# simpleledboard.net
KiCad netlist of a schematic drawn in EAGLE
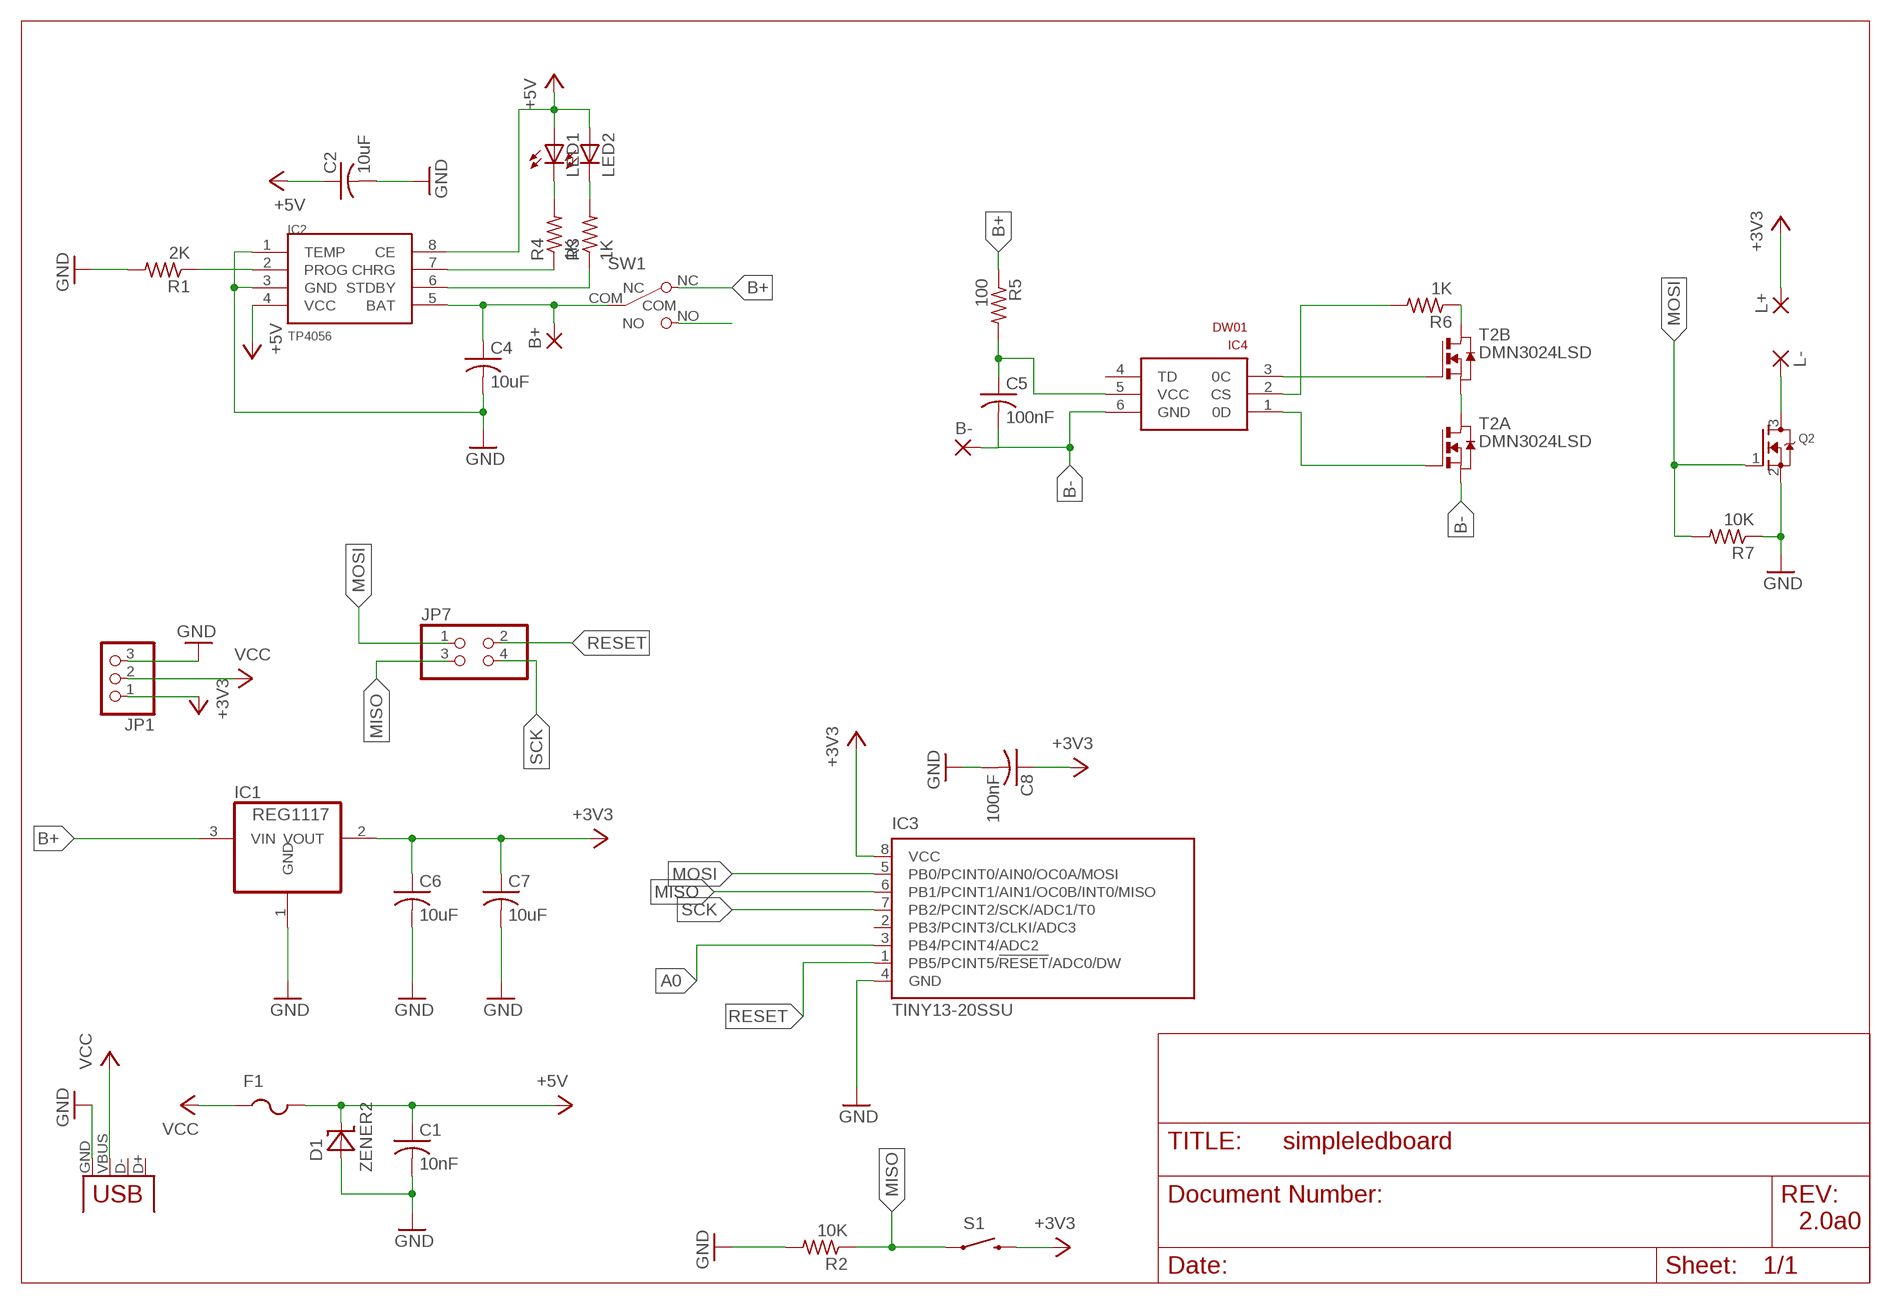
[diagram p0: schematic, sheet 1]

(export (version "E")
  (design (tool "Eeschema 10.0.6"))
  (components
    (comp (ref "B+")
      (value "WIREPADSMD1,27-254")
      (footprint "eagle-import:SMD1,27-2,54")
      (libsource (lib "eagle-import") (part "WIREPADSMD1,27-254"))
    )
    (comp (ref "B-")
      (value "WIREPADSMD1,27-254")
      (footprint "eagle-import:SMD1,27-2,54")
      (libsource (lib "eagle-import") (part "WIREPADSMD1,27-254"))
    )
    (comp (ref "C1")
      (value "10nF")
      (footprint "eagle-import:C0603")
      (libsource (lib "eagle-import") (part "C-USC0603"))
    )
    (comp (ref "C2")
      (value "10uF")
      (footprint "eagle-import:C0603")
      (libsource (lib "eagle-import") (part "C-USC0603"))
    )
    (comp (ref "C4")
      (value "10uF")
      (footprint "eagle-import:C0603")
      (libsource (lib "eagle-import") (part "C-USC0603"))
    )
    (comp (ref "C5")
      (value "100nF")
      (footprint "eagle-import:C0603")
      (libsource (lib "eagle-import") (part "C-USC0603"))
    )
    (comp (ref "C6")
      (value "10uF")
      (footprint "eagle-import:C0603")
      (libsource (lib "eagle-import") (part "C-USC0603"))
    )
    (comp (ref "C7")
      (value "10uF")
      (footprint "eagle-import:C0603")
      (libsource (lib "eagle-import") (part "C-USC0603"))
    )
    (comp (ref "C8")
      (value "100nF")
      (footprint "eagle-import:C0603")
      (libsource (lib "eagle-import") (part "C-USC0603"))
    )
    (comp (ref "D1")
      (value "ZENER2")
      (footprint "eagle-import:SOD123")
      (libsource (lib "eagle-import") (part "ZENER2"))
    )
    (comp (ref "F1")
      (value "PTCFUSE-1206")
      (footprint "eagle-import:R1206")
      (libsource (lib "eagle-import") (part "PTCFUSE-1206"))
    )
    (comp (ref "IC1")
      (value "REG1117")
      (footprint "eagle-import:SOT223")
      (libsource (lib "eagle-import") (part "REG1117"))
    )
    (comp (ref "IC2")
      (value "TP4056")
      (footprint "eagle-import:SOP-8")
      (libsource (lib "eagle-import") (part "TP4056"))
    )
    (comp (ref "IC3")
      (value "TINY13-20SSU")
      (footprint "eagle-import:8S1")
      (fields (field (name "MPN") "ATTINY13-20SSU"))
      (libsource (lib "eagle-import") (part "TINY13SSU-20"))
    )
    (comp (ref "IC4")
      (value "DW01")
      (footprint "eagle-import:SOT23-6")
      (libsource (lib "eagle-import") (part "DW01"))
    )
    (comp (ref "JP1")
      (value "PINHD-1X3CB")
      (footprint "eagle-import:1X03-CLEANBIG")
      (libsource (lib "eagle-import") (part "PINHD-1X3CB"))
    )
    (comp (ref "JP7")
      (value "PINHD-2X2")
      (footprint "eagle-import:2X02")
      (libsource (lib "eagle-import") (part "PINHD-2X2"))
    )
    (comp (ref "L+")
      (value "SMD2")
      (footprint "eagle-import:SMD1,27-2,54")
      (libsource (lib "eagle-import") (part "SMD2"))
    )
    (comp (ref "L-")
      (value "SMD2")
      (footprint "eagle-import:SMD1,27-2,54")
      (libsource (lib "eagle-import") (part "SMD2"))
    )
    (comp (ref "LED1")
      (value "LED0603")
      (footprint "eagle-import:LED-0603")
      (libsource (lib "eagle-import") (part "LED0603"))
    )
    (comp (ref "LED2")
      (value "LED0603")
      (footprint "eagle-import:LED-0603")
      (libsource (lib "eagle-import") (part "LED0603"))
    )
    (comp (ref "Q2")
      (value "MOSFET-NREFLOW")
      (footprint "eagle-import:SOT23")
      (libsource (lib "eagle-import") (part "MOSFET-NREFLOW"))
    )
    (comp (ref "R1")
      (value "2K")
      (footprint "eagle-import:R0603")
      (libsource (lib "eagle-import") (part "R-US_R0603"))
    )
    (comp (ref "R2")
      (value "10K")
      (footprint "eagle-import:R0603")
      (libsource (lib "eagle-import") (part "R-US_R0603"))
    )
    (comp (ref "R3")
      (value "1K")
      (footprint "eagle-import:R0603")
      (libsource (lib "eagle-import") (part "R-US_R0603"))
    )
    (comp (ref "R4")
      (value "1K")
      (footprint "eagle-import:R0603")
      (libsource (lib "eagle-import") (part "R-US_R0603"))
    )
    (comp (ref "R5")
      (value "100")
      (footprint "eagle-import:R1206")
      (libsource (lib "eagle-import") (part "R-US_R1206"))
    )
    (comp (ref "R6")
      (value "1K")
      (footprint "eagle-import:R0603")
      (libsource (lib "eagle-import") (part "R-US_R0603"))
    )
    (comp (ref "R7")
      (value "10K")
      (footprint "eagle-import:R0603")
      (libsource (lib "eagle-import") (part "R-US_R0603"))
    )
    (comp (ref "S1")
      (value "SWITCH-MOMENTARY-2SMD-4.6X2.8MM")
      (footprint "eagle-import:TACTILE_SWITCH_SMD_4.6X2.8MM")
      (libsource (lib "eagle-import") (part "SWITCH-MOMENTARY-2SMD-4.6X2.8MM"))
    )
    (comp (ref "SW1")
      (value "SW_SLIDE")
      (footprint "eagle-import:SLIDE_SWITCH_SMD")
      (libsource (lib "eagle-import") (part "SW_SLIDE"))
    )
    (comp (ref "T2")
      (value "DMN3024LSD")
      (footprint "eagle-import:TSSOP-8")
      (libsource (lib "eagle-import") (part "DMN3024LSD"))
    )
    (comp (ref "X2")
      (value "USB-MICROB")
      (footprint "eagle-import:USB-MICROB")
      (libsource (lib "eagle-import") (part "USB-MICROB"))
    )
  )
  (nets
    (net (code "1") (name "+3V3") (class "Default")
      (node (ref "C6") (pin "1") (pinfunction "1_1") (pintype "passive"))
      (node (ref "C7") (pin "1") (pinfunction "1_1") (pintype "passive"))
      (node (ref "C8") (pin "1") (pinfunction "1_1") (pintype "passive"))
      (node (ref "IC1") (pin "2") (pinfunction "VOUT_2") (pintype "output"))
      (node (ref "IC3") (pin "8") (pinfunction "VCC_8") (pintype "power_in"))
      (node (ref "JP1") (pin "1") (pinfunction "1_1") (pintype "passive"))
      (node (ref "L+") (pin "1") (pinfunction "P_1") (pintype "passive"))
      (node (ref "S1") (pin "3") (pinfunction "2_3") (pintype "passive"))
      (node (ref "S1") (pin "4") (pinfunction "2_4") (pintype "passive"))
    )
    (net (code "2") (name "+5V") (class "Default")
      (node (ref "C1") (pin "1") (pinfunction "1_1") (pintype "passive"))
      (node (ref "C2") (pin "1") (pinfunction "1_1") (pintype "passive"))
      (node (ref "D1") (pin "C") (pinfunction "C_C") (pintype "passive"))
      (node (ref "F1") (pin "2") (pinfunction "2_2") (pintype "passive"))
      (node (ref "IC2") (pin "4") (pinfunction "VCC_4") (pintype "bidirectional"))
      (node (ref "IC2") (pin "8") (pinfunction "CE_8") (pintype "bidirectional"))
      (node (ref "LED1") (pin "A") (pinfunction "A_A") (pintype "passive"))
      (node (ref "LED2") (pin "A") (pinfunction "A_A") (pintype "passive"))
    )
    (net (code "3") (name "A0") (class "Default")
      (node (ref "IC3") (pin "3") (pinfunction "PB4/PCINT4/ADC2_3") (pintype "bidirectional"))
    )
    (net (code "4") (name "B+") (class "Default")
      (node (ref "IC1") (pin "3") (pinfunction "VIN_3") (pintype "input"))
      (node (ref "R5") (pin "1") (pinfunction "1_1") (pintype "passive"))
      (node (ref "SW1") (pin "NC") (pinfunction "NC_NC") (pintype "passive"))
    )
    (net (code "5") (name "B-") (class "Default")
      (node (ref "B-") (pin "1") (pinfunction "P_1") (pintype "passive"))
      (node (ref "C5") (pin "2") (pinfunction "2_2") (pintype "passive"))
      (node (ref "IC4") (pin "6") (pinfunction "GND_6") (pintype "bidirectional"))
      (node (ref "T2") (pin "2") (pinfunction "S_2") (pintype "passive"))
      (node (ref "T2") (pin "3") (pinfunction "S_3") (pintype "passive"))
    )
    (net (code "6") (name "GND") (class "Default")
      (node (ref "C1") (pin "2") (pinfunction "2_2") (pintype "passive"))
      (node (ref "C2") (pin "2") (pinfunction "2_2") (pintype "passive"))
      (node (ref "C4") (pin "2") (pinfunction "2_2") (pintype "passive"))
      (node (ref "C6") (pin "2") (pinfunction "2_2") (pintype "passive"))
      (node (ref "C7") (pin "2") (pinfunction "2_2") (pintype "passive"))
      (node (ref "C8") (pin "2") (pinfunction "2_2") (pintype "passive"))
      (node (ref "D1") (pin "A") (pinfunction "A_A") (pintype "passive"))
      (node (ref "IC1") (pin "1") (pinfunction "GND_1") (pintype "power_in"))
      (node (ref "IC2") (pin "1") (pinfunction "TEMP_1") (pintype "bidirectional"))
      (node (ref "IC2") (pin "3") (pinfunction "GND_3") (pintype "bidirectional"))
      (node (ref "IC3") (pin "4") (pinfunction "GND_4") (pintype "power_in"))
      (node (ref "JP1") (pin "3") (pinfunction "3_3") (pintype "passive"))
      (node (ref "Q2") (pin "2") (pinfunction "S_2") (pintype "bidirectional"))
      (node (ref "R1") (pin "2") (pinfunction "2_2") (pintype "passive"))
      (node (ref "R2") (pin "2") (pinfunction "2_2") (pintype "passive"))
      (node (ref "R7") (pin "1") (pinfunction "1_1") (pintype "passive"))
      (node (ref "X2") (pin "GND") (pinfunction "GND_GND") (pintype "bidirectional"))
    )
    (net (code "7") (name "MISO") (class "Default")
      (node (ref "IC3") (pin "6") (pinfunction "PB1/PCINT1/AIN1/OC0B/INT0/MISO_6") (pintype "bidirectional"))
      (node (ref "JP7") (pin "3") (pinfunction "3_3") (pintype "passive"))
      (node (ref "R2") (pin "1") (pinfunction "1_1") (pintype "passive"))
      (node (ref "S1") (pin "1") (pinfunction "1_1") (pintype "passive"))
      (node (ref "S1") (pin "2") (pinfunction "1_2") (pintype "passive"))
    )
    (net (code "8") (name "MOSI") (class "Default")
      (node (ref "IC3") (pin "5") (pinfunction "PB0/PCINT0/AIN0/OC0A/MOSI_5") (pintype "bidirectional"))
      (node (ref "JP7") (pin "1") (pinfunction "1_1") (pintype "passive"))
      (node (ref "Q2") (pin "1") (pinfunction "G_1") (pintype "bidirectional"))
      (node (ref "R7") (pin "2") (pinfunction "2_2") (pintype "passive"))
    )
    (net (code "9") (name "Net-(B+-P)") (class "Default")
      (node (ref "B+") (pin "1") (pinfunction "P_1") (pintype "passive"))
      (node (ref "C4") (pin "1") (pinfunction "1_1") (pintype "passive"))
      (node (ref "IC2") (pin "5") (pinfunction "BAT_5") (pintype "bidirectional"))
      (node (ref "SW1") (pin "COM") (pinfunction "COM_COM") (pintype "passive"))
    )
    (net (code "10") (name "Net-(IC2-CHRG)") (class "Default")
      (node (ref "IC2") (pin "7") (pinfunction "CHRG_7") (pintype "bidirectional"))
      (node (ref "R4") (pin "1") (pinfunction "1_1") (pintype "passive"))
    )
    (net (code "11") (name "Net-(IC2-PROG)") (class "Default")
      (node (ref "IC2") (pin "2") (pinfunction "PROG_2") (pintype "bidirectional"))
      (node (ref "R1") (pin "1") (pinfunction "1_1") (pintype "passive"))
    )
    (net (code "12") (name "Net-(IC2-STDBY)") (class "Default")
      (node (ref "IC2") (pin "6") (pinfunction "STDBY_6") (pintype "bidirectional"))
      (node (ref "R3") (pin "1") (pinfunction "1_1") (pintype "passive"))
    )
    (net (code "13") (name "Net-(IC4-0C)") (class "Default")
      (node (ref "IC4") (pin "3") (pinfunction "0C_3") (pintype "bidirectional"))
      (node (ref "T2") (pin "5") (pinfunction "G_5") (pintype "passive"))
    )
    (net (code "14") (name "Net-(IC4-0D)") (class "Default")
      (node (ref "IC4") (pin "1") (pinfunction "0D_1") (pintype "bidirectional"))
      (node (ref "T2") (pin "4") (pinfunction "G_4") (pintype "passive"))
    )
    (net (code "15") (name "Net-(IC4-CS)") (class "Default")
      (node (ref "IC4") (pin "2") (pinfunction "CS_2") (pintype "bidirectional"))
      (node (ref "R6") (pin "2") (pinfunction "2_2") (pintype "passive"))
    )
    (net (code "16") (name "Net-(IC4-VCC)") (class "Default")
      (node (ref "C5") (pin "1") (pinfunction "1_1") (pintype "passive"))
      (node (ref "IC4") (pin "5") (pinfunction "VCC_5") (pintype "bidirectional"))
      (node (ref "R5") (pin "2") (pinfunction "2_2") (pintype "passive"))
    )
    (net (code "17") (name "Net-(L--P)") (class "Default")
      (node (ref "L-") (pin "1") (pinfunction "P_1") (pintype "passive"))
      (node (ref "Q2") (pin "3") (pinfunction "D_3") (pintype "bidirectional"))
    )
    (net (code "18") (name "Net-(LED1-PadC)") (class "Default")
      (node (ref "LED1") (pin "C") (pinfunction "C_C") (pintype "passive"))
      (node (ref "R4") (pin "2") (pinfunction "2_2") (pintype "passive"))
    )
    (net (code "19") (name "Net-(LED2-PadC)") (class "Default")
      (node (ref "LED2") (pin "C") (pinfunction "C_C") (pintype "passive"))
      (node (ref "R3") (pin "2") (pinfunction "2_2") (pintype "passive"))
    )
    (net (code "20") (name "Net-(T2A-D)") (class "Default")
      (node (ref "T2") (pin "1") (pinfunction "D_1") (pintype "passive"))
      (node (ref "T2") (pin "6") (pinfunction "S_6") (pintype "passive"))
      (node (ref "T2") (pin "7") (pinfunction "S_7") (pintype "passive"))
    )
    (net (code "21") (name "Net-(T2B-D)") (class "Default")
      (node (ref "R6") (pin "1") (pinfunction "1_1") (pintype "passive"))
      (node (ref "T2") (pin "8") (pinfunction "D_8") (pintype "passive"))
    )
    (net (code "22") (name "RESET") (class "Default")
      (node (ref "IC3") (pin "1") (pinfunction "PB5/PCINT5/~{RESET}/ADC0/DW_1") (pintype "bidirectional"))
      (node (ref "JP7") (pin "2") (pinfunction "2_2") (pintype "passive"))
    )
    (net (code "23") (name "SCK") (class "Default")
      (node (ref "IC3") (pin "7") (pinfunction "PB2/PCINT2/SCK/ADC1/T0_7") (pintype "bidirectional"))
      (node (ref "JP7") (pin "4") (pinfunction "4_4") (pintype "passive"))
    )
    (net (code "24") (name "VCC") (class "Default")
      (node (ref "F1") (pin "1") (pinfunction "1_1") (pintype "passive"))
      (node (ref "JP1") (pin "2") (pinfunction "2_2") (pintype "passive"))
      (node (ref "X2") (pin "VBUS") (pinfunction "VBUS_VBUS") (pintype "bidirectional"))
    )
    (net (code "25") (name "unconnected-(IC3-PB3{slash}PCINT3{slash}CLKI{slash}ADC3-Pad2)") (class "Default")
      (node (ref "IC3") (pin "2") (pinfunction "PB3/PCINT3/CLKI/ADC3_2") (pintype "bidirectional"))
    )
    (net (code "26") (name "unconnected-(IC4-TD-Pad4)") (class "Default")
      (node (ref "IC4") (pin "4") (pinfunction "TD_4") (pintype "bidirectional"))
    )
    (net (code "27") (name "unconnected-(SW1-PadNO)") (class "Default")
      (node (ref "SW1") (pin "NO") (pinfunction "NO_NO") (pintype "passive"))
    )
    (net (code "28") (name "unconnected-(X2-PadD+)") (class "Default")
      (node (ref "X2") (pin "D+") (pinfunction "D+_D+") (pintype "bidirectional"))
    )
    (net (code "29") (name "unconnected-(X2-PadD-)") (class "Default")
      (node (ref "X2") (pin "D-") (pinfunction "D-_D-") (pintype "bidirectional"))
    )
  )
)
